# scheme.net
KiCad netlist of a schematic drawn in EAGLE
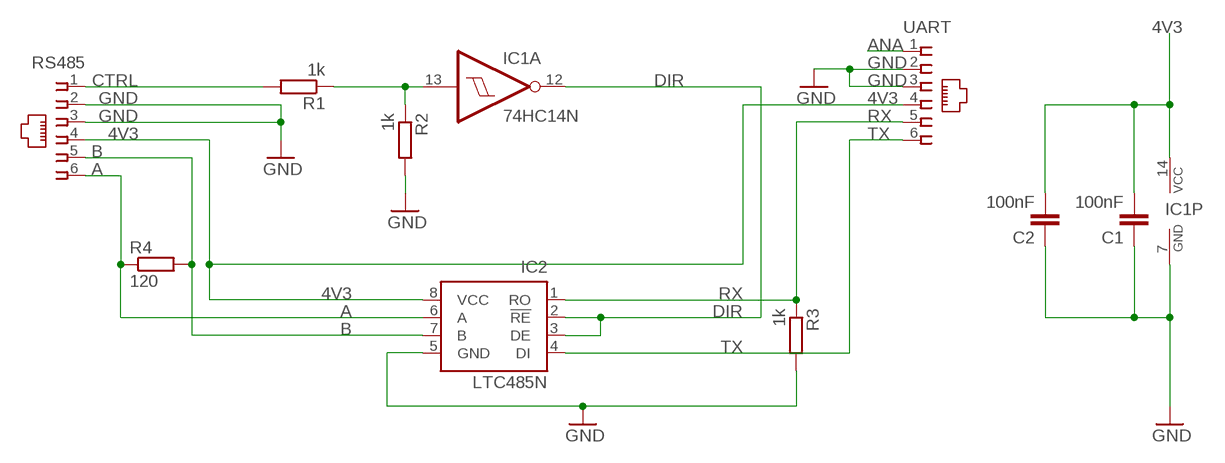
[diagram p0: schematic, sheet 1]

(export (version "E")
  (design (tool "Eeschema 10.0.6"))
  (components
    (comp (ref "C1")
      (value "100nF")
      (footprint "eagle-import:C050-024X044")
      (libsource (lib "eagle-import") (part "C-EU050-024X044"))
    )
    (comp (ref "C2")
      (value "100nF")
      (footprint "eagle-import:C050-024X044")
      (libsource (lib "eagle-import") (part "C-EU050-024X044"))
    )
    (comp (ref "IC1")
      (value "74HC14N")
      (footprint "eagle-import:DIL14")
      (libsource (lib "eagle-import") (part "7414NHC"))
    )
    (comp (ref "IC2")
      (value "LTC485N")
      (footprint "eagle-import:DIL08")
      (libsource (lib "eagle-import") (part "LTC485N"))
    )
    (comp (ref "R1")
      (value "1k")
      (footprint "eagle-import:0204_7")
      (libsource (lib "eagle-import") (part "R-EU_0204/7"))
    )
    (comp (ref "R2")
      (value "1k")
      (footprint "eagle-import:0204_7")
      (libsource (lib "eagle-import") (part "R-EU_0204/7"))
    )
    (comp (ref "R3")
      (value "1k")
      (footprint "eagle-import:0204_7")
      (libsource (lib "eagle-import") (part "R-EU_0204/7"))
    )
    (comp (ref "R4")
      (value "120")
      (footprint "eagle-import:0204_7")
      (libsource (lib "eagle-import") (part "R-EU_0204/7"))
    )
    (comp (ref "RS485")
      (value "NXT")
      (footprint "eagle-import:NXT")
      (libsource (lib "eagle-import") (part "NXT"))
    )
    (comp (ref "UART")
      (value "NXT")
      (footprint "eagle-import:NXT")
      (libsource (lib "eagle-import") (part "NXT"))
    )
  )
  (nets
    (net (code "1") (name "/4V3") (class "Default")
      (node (ref "C1") (pin "2") (pinfunction "2_2") (pintype "passive"))
      (node (ref "C2") (pin "2") (pinfunction "2_2") (pintype "passive"))
      (node (ref "IC1") (pin "14") (pinfunction "VCC_14") (pintype "power_in"))
      (node (ref "IC2") (pin "8") (pinfunction "VCC_8") (pintype "input"))
      (node (ref "RS485") (pin "4") (pinfunction "4_4") (pintype "passive"))
      (node (ref "UART") (pin "4") (pinfunction "4_4") (pintype "passive"))
    )
    (net (code "2") (name "/A") (class "Default")
      (node (ref "IC2") (pin "6") (pinfunction "A_6") (pintype "bidirectional"))
      (node (ref "R4") (pin "1") (pinfunction "1_1") (pintype "passive"))
      (node (ref "RS485") (pin "6") (pinfunction "6_6") (pintype "passive"))
    )
    (net (code "3") (name "/ANA") (class "Default")
      (node (ref "UART") (pin "1") (pinfunction "1_1") (pintype "passive"))
    )
    (net (code "4") (name "/B") (class "Default")
      (node (ref "IC2") (pin "7") (pinfunction "B_7") (pintype "bidirectional"))
      (node (ref "R4") (pin "2") (pinfunction "2_2") (pintype "passive"))
      (node (ref "RS485") (pin "5") (pinfunction "5_5") (pintype "passive"))
    )
    (net (code "5") (name "/CTRL") (class "Default")
      (node (ref "R1") (pin "2") (pinfunction "2_2") (pintype "passive"))
      (node (ref "RS485") (pin "1") (pinfunction "1_1") (pintype "passive"))
    )
    (net (code "6") (name "/DIR") (class "Default")
      (node (ref "IC1") (pin "12") (pinfunction "O_12") (pintype "output"))
      (node (ref "IC2") (pin "2") (pinfunction "~{RE}_2") (pintype "input"))
      (node (ref "IC2") (pin "3") (pinfunction "DE_3") (pintype "input"))
    )
    (net (code "7") (name "/RX") (class "Default")
      (node (ref "IC2") (pin "1") (pinfunction "RO_1") (pintype "output"))
      (node (ref "R3") (pin "1") (pinfunction "1_1") (pintype "passive"))
      (node (ref "UART") (pin "5") (pinfunction "5_5") (pintype "passive"))
    )
    (net (code "8") (name "/TX") (class "Default")
      (node (ref "IC2") (pin "4") (pinfunction "DI_4") (pintype "input"))
      (node (ref "UART") (pin "6") (pinfunction "6_6") (pintype "passive"))
    )
    (net (code "9") (name "GND") (class "Default")
      (node (ref "C1") (pin "1") (pinfunction "1_1") (pintype "passive"))
      (node (ref "C2") (pin "1") (pinfunction "1_1") (pintype "passive"))
      (node (ref "IC1") (pin "7") (pinfunction "GND_7") (pintype "power_in"))
      (node (ref "IC2") (pin "5") (pinfunction "GND_5") (pintype "input"))
      (node (ref "R2") (pin "2") (pinfunction "2_2") (pintype "passive"))
      (node (ref "R3") (pin "2") (pinfunction "2_2") (pintype "passive"))
      (node (ref "RS485") (pin "2") (pinfunction "2_2") (pintype "passive"))
      (node (ref "RS485") (pin "3") (pinfunction "3_3") (pintype "passive"))
      (node (ref "UART") (pin "2") (pinfunction "2_2") (pintype "passive"))
      (node (ref "UART") (pin "3") (pinfunction "3_3") (pintype "passive"))
    )
    (net (code "10") (name "Net-(IC1A-I)") (class "Default")
      (node (ref "IC1") (pin "13") (pinfunction "I_13") (pintype "input"))
      (node (ref "R1") (pin "1") (pinfunction "1_1") (pintype "passive"))
      (node (ref "R2") (pin "1") (pinfunction "1_1") (pintype "passive"))
    )
  )
)
